# vendotron_v1.net
KiCad netlist of a schematic drawn in EAGLE
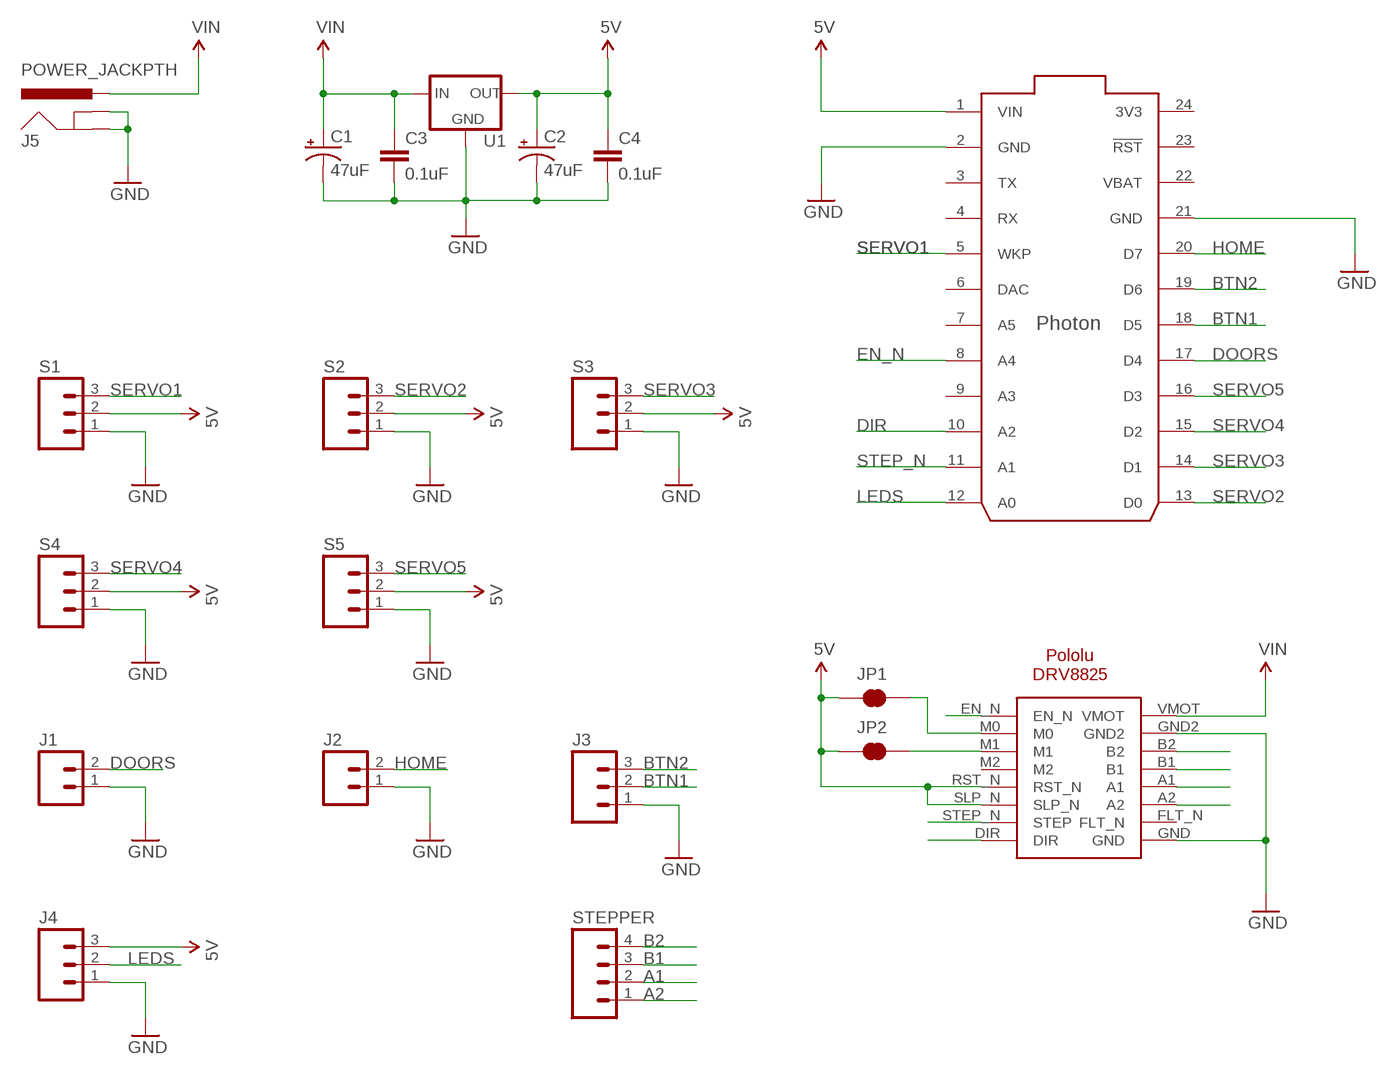
[diagram p0: schematic, sheet 1]

(export (version "E")
  (design (tool "Eeschema 10.0.6"))
  (components
    (comp (ref "C1")
      (value "47uF")
      (footprint "eagle-import:CPOL-RADIAL-10UF-25V")
      (libsource (lib "eagle-import") (part "CAP_POLPTH2"))
    )
    (comp (ref "C2")
      (value "47uF")
      (footprint "eagle-import:CPOL-RADIAL-10UF-25V")
      (libsource (lib "eagle-import") (part "CAP_POLPTH2"))
    )
    (comp (ref "C3")
      (value "0.1uF")
      (footprint "eagle-import:CAP-PTH-SMALL")
      (libsource (lib "eagle-import") (part "CAPPTH"))
    )
    (comp (ref "C4")
      (value "0.1uF")
      (footprint "eagle-import:CAP-PTH-SMALL")
      (libsource (lib "eagle-import") (part "CAPPTH"))
    )
    (comp (ref "J1")
      (value "M023.5MM")
      (footprint "eagle-import:SCREWTERMINAL-3.5MM-2")
      (libsource (lib "eagle-import") (part "M023.5MM"))
    )
    (comp (ref "J2")
      (value "M023.5MM")
      (footprint "eagle-import:SCREWTERMINAL-3.5MM-2")
      (libsource (lib "eagle-import") (part "M023.5MM"))
    )
    (comp (ref "J3")
      (value "M03SCREW")
      (footprint "eagle-import:SCREWTERMINAL-3.5MM-3")
      (libsource (lib "eagle-import") (part "M03SCREW"))
    )
    (comp (ref "J4")
      (value "M03SCREW")
      (footprint "eagle-import:SCREWTERMINAL-3.5MM-3")
      (libsource (lib "eagle-import") (part "M03SCREW"))
    )
    (comp (ref "J5")
      (value "POWER_JACKPTH")
      (footprint "eagle-import:POWER_JACK_PTH")
      (libsource (lib "eagle-import") (part "POWER_JACKPTH"))
    )
    (comp (ref "JP1")
      (value "JUMPER-PAD-2-NC_BY_TRACE")
      (footprint "eagle-import:PAD-JUMPER-2-NC_BY_TRACE_YES_SILK")
      (libsource (lib "eagle-import") (part "JUMPER-PAD-2-NC_BY_TRACE"))
    )
    (comp (ref "JP2")
      (value "JUMPER-PAD-2-NC_BY_TRACE")
      (footprint "eagle-import:PAD-JUMPER-2-NC_BY_TRACE_YES_SILK")
      (libsource (lib "eagle-import") (part "JUMPER-PAD-2-NC_BY_TRACE"))
    )
    (comp (ref "S1")
      (value "M03PTH")
      (footprint "eagle-import:1X03")
      (libsource (lib "eagle-import") (part "M03PTH"))
    )
    (comp (ref "S2")
      (value "M03PTH")
      (footprint "eagle-import:1X03")
      (libsource (lib "eagle-import") (part "M03PTH"))
    )
    (comp (ref "S3")
      (value "M03PTH")
      (footprint "eagle-import:1X03")
      (libsource (lib "eagle-import") (part "M03PTH"))
    )
    (comp (ref "S4")
      (value "M03PTH")
      (footprint "eagle-import:1X03")
      (libsource (lib "eagle-import") (part "M03PTH"))
    )
    (comp (ref "S5")
      (value "M03PTH")
      (footprint "eagle-import:1X03")
      (libsource (lib "eagle-import") (part "M03PTH"))
    )
    (comp (ref "STEPPER")
      (value "M04SCREW")
      (footprint "eagle-import:SCREWTERMINAL-3.5MM-4")
      (libsource (lib "eagle-import") (part "M04SCREW"))
    )
    (comp (ref "U$1")
      (value "PHOTON_WITH_HEADERS")
      (footprint "eagle-import:PHOTON")
      (libsource (lib "eagle-import") (part "PHOTON_WITH_HEADERS"))
    )
    (comp (ref "U$2")
      (value "POLOLU-DRV8825")
      (footprint "eagle-import:POLOLU-DRV8825")
      (libsource (lib "eagle-import") (part "POLOLU-DRV8825"))
    )
    (comp (ref "U1")
      (value "V_REG_78XXSINK")
      (footprint "eagle-import:TO220-IGO")
      (libsource (lib "eagle-import") (part "V_REG_78XXSINK"))
    )
  )
  (nets
    (net (code "1") (name "/3V3") (class "Default")
      (node (ref "U$1") (pin "24") (pinfunction "3V3_24") (pintype "power_in"))
    )
    (net (code "2") (name "/A1") (class "Default")
      (node (ref "STEPPER") (pin "2") (pinfunction "2_2") (pintype "passive"))
      (node (ref "U$2") (pin "A1") (pinfunction "A1_A1") (pintype "bidirectional"))
    )
    (net (code "3") (name "/A2") (class "Default")
      (node (ref "STEPPER") (pin "1") (pinfunction "1_1") (pintype "passive"))
      (node (ref "U$2") (pin "A2") (pinfunction "A2_A2") (pintype "bidirectional"))
    )
    (net (code "4") (name "/B1") (class "Default")
      (node (ref "STEPPER") (pin "3") (pinfunction "3_3") (pintype "passive"))
      (node (ref "U$2") (pin "B1") (pinfunction "B1_B1") (pintype "bidirectional"))
    )
    (net (code "5") (name "/B2") (class "Default")
      (node (ref "STEPPER") (pin "4") (pinfunction "4_4") (pintype "passive"))
      (node (ref "U$2") (pin "B2") (pinfunction "B2_B2") (pintype "bidirectional"))
    )
    (net (code "6") (name "/BTN1") (class "Default")
      (node (ref "J3") (pin "2") (pinfunction "2_2") (pintype "passive"))
      (node (ref "U$1") (pin "18") (pinfunction "D5_18") (pintype "bidirectional"))
    )
    (net (code "7") (name "/BTN2") (class "Default")
      (node (ref "J3") (pin "3") (pinfunction "3_3") (pintype "passive"))
      (node (ref "U$1") (pin "19") (pinfunction "D6_19") (pintype "bidirectional"))
    )
    (net (code "8") (name "/DIR") (class "Default")
      (node (ref "U$1") (pin "10") (pinfunction "A2_10") (pintype "bidirectional"))
      (node (ref "U$2") (pin "DIR") (pinfunction "DIR_DIR") (pintype "bidirectional"))
    )
    (net (code "9") (name "/DOORS") (class "Default")
      (node (ref "J1") (pin "2") (pinfunction "2_2") (pintype "passive"))
      (node (ref "U$1") (pin "17") (pinfunction "D4_17") (pintype "bidirectional"))
    )
    (net (code "10") (name "/EN_N") (class "Default")
      (node (ref "U$1") (pin "8") (pinfunction "A4_8") (pintype "bidirectional"))
      (node (ref "U$2") (pin "EN_N") (pinfunction "EN_N_EN_N") (pintype "bidirectional"))
    )
    (net (code "11") (name "/HOME") (class "Default")
      (node (ref "J2") (pin "2") (pinfunction "2_2") (pintype "passive"))
      (node (ref "U$1") (pin "20") (pinfunction "D7_20") (pintype "bidirectional"))
    )
    (net (code "12") (name "/LEDS") (class "Default")
      (node (ref "J4") (pin "2") (pinfunction "2_2") (pintype "passive"))
      (node (ref "U$1") (pin "12") (pinfunction "A0_12") (pintype "bidirectional"))
    )
    (net (code "13") (name "/SERVO1") (class "Default")
      (node (ref "S1") (pin "3") (pinfunction "3_3") (pintype "passive"))
      (node (ref "U$1") (pin "5") (pinfunction "WKP_5") (pintype "bidirectional"))
    )
    (net (code "14") (name "/SERVO2") (class "Default")
      (node (ref "S2") (pin "3") (pinfunction "3_3") (pintype "passive"))
      (node (ref "U$1") (pin "13") (pinfunction "D0_13") (pintype "bidirectional"))
    )
    (net (code "15") (name "/SERVO3") (class "Default")
      (node (ref "S3") (pin "3") (pinfunction "3_3") (pintype "passive"))
      (node (ref "U$1") (pin "14") (pinfunction "D1_14") (pintype "bidirectional"))
    )
    (net (code "16") (name "/SERVO4") (class "Default")
      (node (ref "S4") (pin "3") (pinfunction "3_3") (pintype "passive"))
      (node (ref "U$1") (pin "15") (pinfunction "D2_15") (pintype "bidirectional"))
    )
    (net (code "17") (name "/SERVO5") (class "Default")
      (node (ref "S5") (pin "3") (pinfunction "3_3") (pintype "passive"))
      (node (ref "U$1") (pin "16") (pinfunction "D3_16") (pintype "bidirectional"))
    )
    (net (code "18") (name "/STEP_N") (class "Default")
      (node (ref "U$1") (pin "11") (pinfunction "A1_11") (pintype "bidirectional"))
      (node (ref "U$2") (pin "STEP_N") (pinfunction "STEP_STEP_N") (pintype "bidirectional"))
    )
    (net (code "19") (name "/VBAT") (class "Default")
      (node (ref "U$1") (pin "22") (pinfunction "VBAT_22") (pintype "power_in"))
    )
    (net (code "20") (name "5V") (class "Default")
      (node (ref "C2") (pin "1") (pinfunction "+_1") (pintype "passive"))
      (node (ref "C4") (pin "1") (pinfunction "1_1") (pintype "passive"))
      (node (ref "J4") (pin "3") (pinfunction "3_3") (pintype "passive"))
      (node (ref "JP1") (pin "1") (pinfunction "1_1") (pintype "passive"))
      (node (ref "JP2") (pin "1") (pinfunction "1_1") (pintype "passive"))
      (node (ref "S1") (pin "2") (pinfunction "2_2") (pintype "passive"))
      (node (ref "S2") (pin "2") (pinfunction "2_2") (pintype "passive"))
      (node (ref "S3") (pin "2") (pinfunction "2_2") (pintype "passive"))
      (node (ref "S4") (pin "2") (pinfunction "2_2") (pintype "passive"))
      (node (ref "S5") (pin "2") (pinfunction "2_2") (pintype "passive"))
      (node (ref "U$1") (pin "1") (pinfunction "VIN_1") (pintype "power_in"))
      (node (ref "U$2") (pin "RST_N") (pinfunction "RST_N_RST_N") (pintype "bidirectional"))
      (node (ref "U$2") (pin "SLP_N") (pinfunction "SLP_N_SLP_N") (pintype "bidirectional"))
      (node (ref "U1") (pin "OUT") (pinfunction "OUT_OUT") (pintype "passive"))
    )
    (net (code "21") (name "GND") (class "Default")
      (node (ref "C1") (pin "2") (pinfunction "-_2") (pintype "passive"))
      (node (ref "C2") (pin "2") (pinfunction "-_2") (pintype "passive"))
      (node (ref "C3") (pin "2") (pinfunction "2_2") (pintype "passive"))
      (node (ref "C4") (pin "2") (pinfunction "2_2") (pintype "passive"))
      (node (ref "J1") (pin "1") (pinfunction "1_1") (pintype "passive"))
      (node (ref "J2") (pin "1") (pinfunction "1_1") (pintype "passive"))
      (node (ref "J3") (pin "1") (pinfunction "1_1") (pintype "passive"))
      (node (ref "J4") (pin "1") (pinfunction "1_1") (pintype "passive"))
      (node (ref "J5") (pin "GND") (pinfunction "GND_GND") (pintype "bidirectional"))
      (node (ref "J5") (pin "GNDBREAK") (pinfunction "GNDBREAK_GNDBREAK") (pintype "bidirectional"))
      (node (ref "S1") (pin "1") (pinfunction "1_1") (pintype "passive"))
      (node (ref "S2") (pin "1") (pinfunction "1_1") (pintype "passive"))
      (node (ref "S3") (pin "1") (pinfunction "1_1") (pintype "passive"))
      (node (ref "S4") (pin "1") (pinfunction "1_1") (pintype "passive"))
      (node (ref "S5") (pin "1") (pinfunction "1_1") (pintype "passive"))
      (node (ref "U$1") (pin "2") (pinfunction "GND_2") (pintype "power_in"))
      (node (ref "U$1") (pin "21") (pinfunction "GND_21") (pintype "power_in"))
      (node (ref "U$2") (pin "GND") (pinfunction "GND_GND") (pintype "bidirectional"))
      (node (ref "U$2") (pin "GND2") (pinfunction "GND2_GND2") (pintype "bidirectional"))
      (node (ref "U1") (pin "GND") (pinfunction "GND_GND") (pintype "input"))
    )
    (net (code "22") (name "Net-(JP1-Pad2)") (class "Default")
      (node (ref "JP1") (pin "2") (pinfunction "2_2") (pintype "passive"))
      (node (ref "U$2") (pin "M0") (pinfunction "M0_M0") (pintype "bidirectional"))
    )
    (net (code "23") (name "Net-(JP2-Pad2)") (class "Default")
      (node (ref "JP2") (pin "2") (pinfunction "2_2") (pintype "passive"))
      (node (ref "U$2") (pin "M1") (pinfunction "M1_M1") (pintype "bidirectional"))
    )
    (net (code "24") (name "VIN") (class "Default")
      (node (ref "C1") (pin "1") (pinfunction "+_1") (pintype "passive"))
      (node (ref "C3") (pin "1") (pinfunction "1_1") (pintype "passive"))
      (node (ref "J5") (pin "PWR") (pinfunction "PWR_PWR") (pintype "bidirectional"))
      (node (ref "U$2") (pin "VMOT") (pinfunction "VMOT_VMOT") (pintype "bidirectional"))
      (node (ref "U1") (pin "IN") (pinfunction "IN_IN") (pintype "input"))
    )
    (net (code "25") (name "unconnected-(U$1-A3-Pad9)") (class "Default")
      (node (ref "U$1") (pin "9") (pinfunction "A3_9") (pintype "bidirectional"))
    )
    (net (code "26") (name "unconnected-(U$1-A5-Pad7)") (class "Default")
      (node (ref "U$1") (pin "7") (pinfunction "A5_7") (pintype "bidirectional"))
    )
    (net (code "27") (name "unconnected-(U$1-DAC-Pad6)") (class "Default")
      (node (ref "U$1") (pin "6") (pinfunction "DAC_6") (pintype "bidirectional"))
    )
    (net (code "28") (name "unconnected-(U$1-RX-Pad4)") (class "Default")
      (node (ref "U$1") (pin "4") (pinfunction "RX_4") (pintype "bidirectional"))
    )
    (net (code "29") (name "unconnected-(U$1-TX-Pad3)") (class "Default")
      (node (ref "U$1") (pin "3") (pinfunction "TX_3") (pintype "bidirectional"))
    )
    (net (code "30") (name "unconnected-(U$1-~{RST}-Pad23)") (class "Default")
      (node (ref "U$1") (pin "23") (pinfunction "~{RST}_23") (pintype "bidirectional"))
    )
    (net (code "31") (name "unconnected-(U$2-PadFLT_N)") (class "Default")
      (node (ref "U$2") (pin "FLT_N") (pinfunction "FLT_N_FLT_N") (pintype "bidirectional"))
    )
    (net (code "32") (name "unconnected-(U$2-PadM2)") (class "Default")
      (node (ref "U$2") (pin "M2") (pinfunction "M2_M2") (pintype "bidirectional"))
    )
  )
)
